# ptn_eagle7x.net
KiCad netlist of a schematic drawn in EAGLE
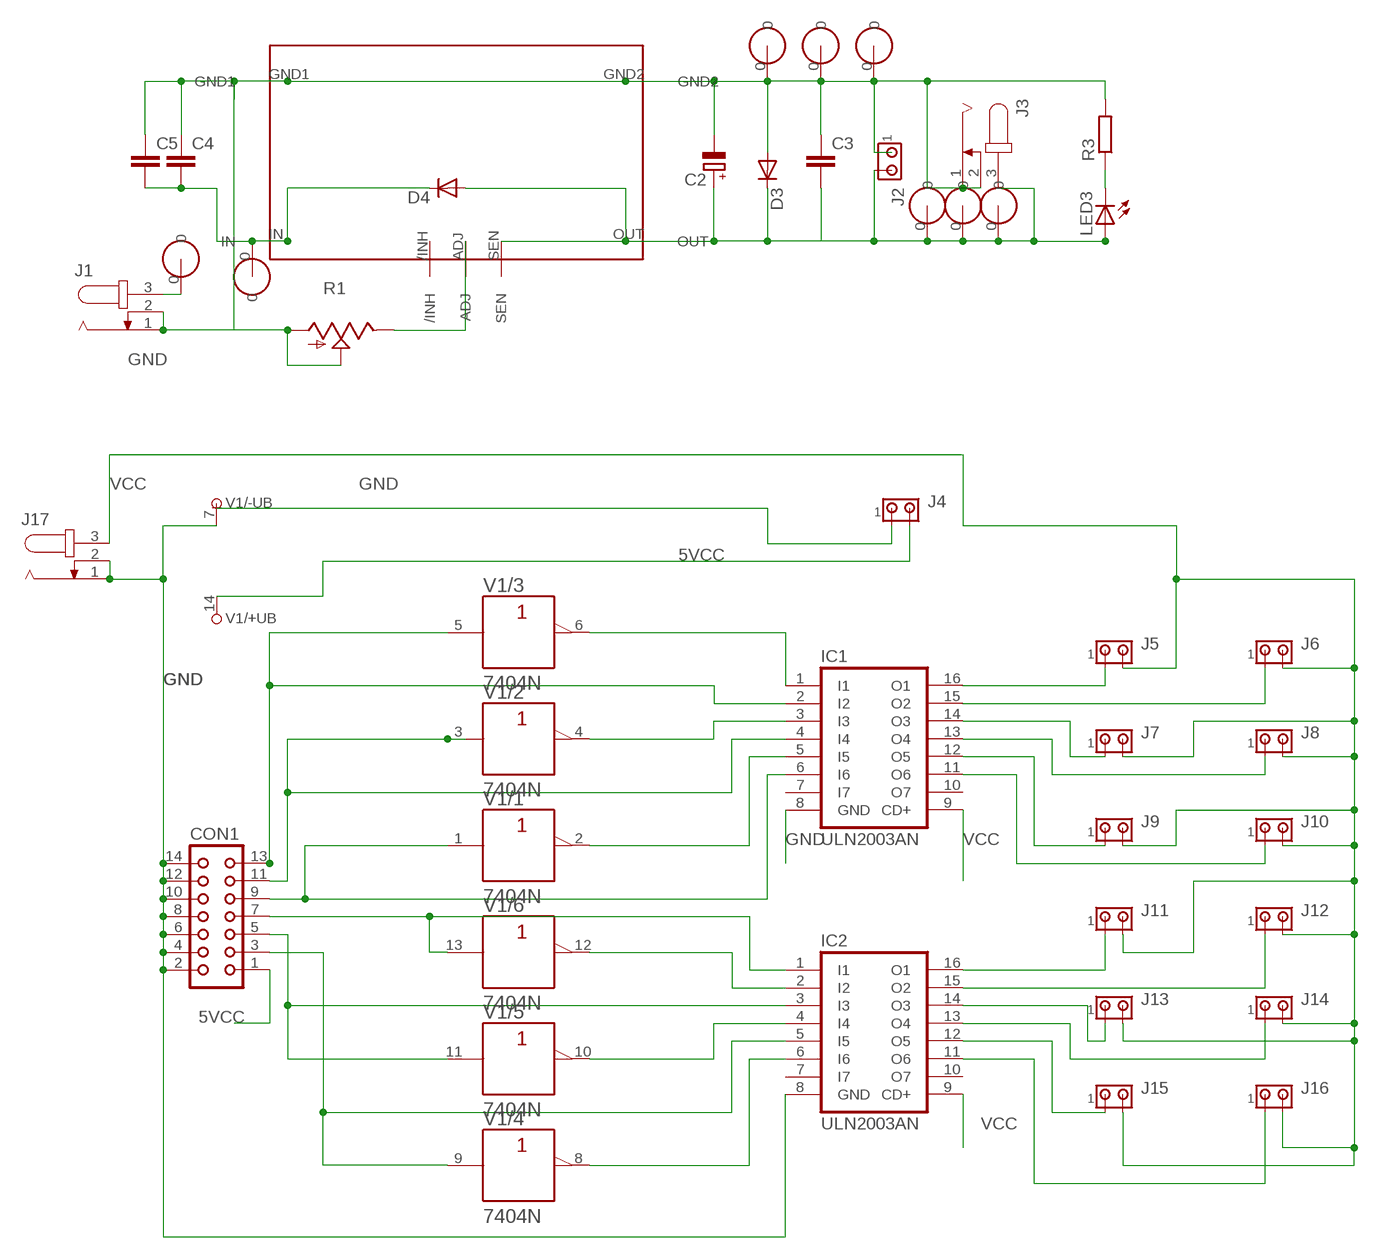
[diagram p0: schematic, sheet 1]

(export (version "E")
  (design (tool "Eeschema 10.0.6"))
  (components
    (comp (ref "C2")
      (value "CPOL-EUE3.5-8")
      (footprint "eagle-import:E3,5-8")
      (libsource (lib "eagle-import") (part "CPOL-EUE3.5-8"))
    )
    (comp (ref "C3")
      (value "C-EUC1206K")
      (footprint "eagle-import:C1206K")
      (libsource (lib "eagle-import") (part "C-EUC1206K"))
    )
    (comp (ref "C4")
      (value "C-EUC1206K")
      (footprint "eagle-import:C1206K")
      (libsource (lib "eagle-import") (part "C-EUC1206K"))
    )
    (comp (ref "C5")
      (value "C-EUC1206K")
      (footprint "eagle-import:C1206K")
      (libsource (lib "eagle-import") (part "C-EUC1206K"))
    )
    (comp (ref "CON1")
      (value "CON14")
      (footprint "eagle-import:CON14")
      (libsource (lib "eagle-import") (part "CON14"))
    )
    (comp (ref "D3")
      (value "DIODE-SMB")
      (footprint "eagle-import:SMB")
      (libsource (lib "eagle-import") (part "DIODE-SMB"))
    )
    (comp (ref "D4")
      (value "DIODE-SMB")
      (footprint "eagle-import:SMB")
      (libsource (lib "eagle-import") (part "DIODE-SMB"))
    )
    (comp (ref "IC1")
      (value "ULN2003AN")
      (footprint "eagle-import:DIL16")
      (libsource (lib "eagle-import") (part "ULN2003AN"))
    )
    (comp (ref "IC2")
      (value "ULN2003AN")
      (footprint "eagle-import:DIL16")
      (libsource (lib "eagle-import") (part "ULN2003AN"))
    )
    (comp (ref "J1")
      (value "JACK-PLUG1")
      (footprint "eagle-import:SPC4078")
      (libsource (lib "eagle-import") (part "JACK-PLUG1"))
    )
    (comp (ref "J2")
      (value "MTA02-100")
      (footprint "eagle-import:10X02MTA")
      (libsource (lib "eagle-import") (part "MTA02-100"))
    )
    (comp (ref "J3")
      (value "JACK-PLUG1")
      (footprint "eagle-import:SPC4078")
      (libsource (lib "eagle-import") (part "JACK-PLUG1"))
    )
    (comp (ref "J4")
      (value "MTA02-100")
      (footprint "eagle-import:10X02MTA")
      (libsource (lib "eagle-import") (part "MTA02-100"))
    )
    (comp (ref "J5")
      (value "MTA02-100")
      (footprint "eagle-import:10X02MTA")
      (libsource (lib "eagle-import") (part "MTA02-100"))
    )
    (comp (ref "J6")
      (value "MTA02-100")
      (footprint "eagle-import:10X02MTA")
      (libsource (lib "eagle-import") (part "MTA02-100"))
    )
    (comp (ref "J7")
      (value "MTA02-100")
      (footprint "eagle-import:10X02MTA")
      (libsource (lib "eagle-import") (part "MTA02-100"))
    )
    (comp (ref "J8")
      (value "MTA02-100")
      (footprint "eagle-import:10X02MTA")
      (libsource (lib "eagle-import") (part "MTA02-100"))
    )
    (comp (ref "J9")
      (value "MTA02-100")
      (footprint "eagle-import:10X02MTA")
      (libsource (lib "eagle-import") (part "MTA02-100"))
    )
    (comp (ref "J10")
      (value "MTA02-100")
      (footprint "eagle-import:10X02MTA")
      (libsource (lib "eagle-import") (part "MTA02-100"))
    )
    (comp (ref "J11")
      (value "MTA02-100")
      (footprint "eagle-import:10X02MTA")
      (libsource (lib "eagle-import") (part "MTA02-100"))
    )
    (comp (ref "J12")
      (value "MTA02-100")
      (footprint "eagle-import:10X02MTA")
      (libsource (lib "eagle-import") (part "MTA02-100"))
    )
    (comp (ref "J13")
      (value "MTA02-100")
      (footprint "eagle-import:10X02MTA")
      (libsource (lib "eagle-import") (part "MTA02-100"))
    )
    (comp (ref "J14")
      (value "MTA02-100")
      (footprint "eagle-import:10X02MTA")
      (libsource (lib "eagle-import") (part "MTA02-100"))
    )
    (comp (ref "J15")
      (value "MTA02-100")
      (footprint "eagle-import:10X02MTA")
      (libsource (lib "eagle-import") (part "MTA02-100"))
    )
    (comp (ref "J16")
      (value "MTA02-100")
      (footprint "eagle-import:10X02MTA")
      (libsource (lib "eagle-import") (part "MTA02-100"))
    )
    (comp (ref "J17")
      (value "JACK-PLUG1")
      (footprint "eagle-import:SPC4078")
      (libsource (lib "eagle-import") (part "JACK-PLUG1"))
    )
    (comp (ref "LED3")
      (value "LED3MM")
      (footprint "eagle-import:LED3MM")
      (libsource (lib "eagle-import") (part "LED3MM"))
    )
    (comp (ref "R1")
      (value "TRIM_US-B64Y")
      (footprint "eagle-import:B64Y")
      (libsource (lib "eagle-import") (part "TRIM_US-B64Y"))
    )
    (comp (ref "R3")
      (value "R-EU_R0603")
      (footprint "eagle-import:R0603")
      (libsource (lib "eagle-import") (part "R-EU_R0603"))
    )
    (comp (ref "U$1")
      (value "PTNPTN2")
      (footprint "eagle-import:PTN")
      (libsource (lib "eagle-import") (part "PTNPTN2"))
    )
    (comp (ref "U$2")
      (value "PAD0")
      (footprint "eagle-import:SWITCHPAD")
      (libsource (lib "eagle-import") (part "PAD0"))
    )
    (comp (ref "U$3")
      (value "PADSWITCHPAD1")
      (footprint "eagle-import:SWITCHPAD")
      (libsource (lib "eagle-import") (part "PADSWITCHPAD1"))
    )
    (comp (ref "U$4")
      (value "PADSWITCHPAD1")
      (footprint "eagle-import:SWITCHPAD")
      (libsource (lib "eagle-import") (part "PADSWITCHPAD1"))
    )
    (comp (ref "U$5")
      (value "PADSWITCHPAD1")
      (footprint "eagle-import:SWITCHPAD")
      (libsource (lib "eagle-import") (part "PADSWITCHPAD1"))
    )
    (comp (ref "U$6")
      (value "PADSWITCHPAD1")
      (footprint "eagle-import:SWITCHPAD")
      (libsource (lib "eagle-import") (part "PADSWITCHPAD1"))
    )
    (comp (ref "U$7")
      (value "PADSWITCHPAD1")
      (footprint "eagle-import:SWITCHPAD")
      (libsource (lib "eagle-import") (part "PADSWITCHPAD1"))
    )
    (comp (ref "U$8")
      (value "PADSWITCHPAD1")
      (footprint "eagle-import:SWITCHPAD")
      (libsource (lib "eagle-import") (part "PADSWITCHPAD1"))
    )
    (comp (ref "U$9")
      (value "PADSWITCHPAD1")
      (footprint "eagle-import:SWITCHPAD")
      (libsource (lib "eagle-import") (part "PADSWITCHPAD1"))
    )
    (comp (ref "V1")
      (value "7404N")
      (footprint "eagle-import:DIL14")
      (libsource (lib "eagle-import") (part "7404N"))
    )
  )
  (nets
    (net (code "1") (name "/5VCC") (class "Default")
      (node (ref "CON1") (pin "1") (pinfunction "1_1") (pintype "passive"))
      (node (ref "J4") (pin "2") (pinfunction "2_2") (pintype "passive"))
      (node (ref "V1") (pin "14") (pinfunction "+UB_14") (pintype "power_in"))
    )
    (net (code "2") (name "/GND") (class "Default")
      (node (ref "C2") (pin "-") (pinfunction "-_-") (pintype "passive"))
      (node (ref "C3") (pin "1") (pinfunction "1_1") (pintype "passive"))
      (node (ref "C4") (pin "1") (pinfunction "1_1") (pintype "passive"))
      (node (ref "C5") (pin "1") (pinfunction "1_1") (pintype "passive"))
      (node (ref "CON1") (pin "10") (pinfunction "10_10") (pintype "passive"))
      (node (ref "CON1") (pin "12") (pinfunction "12_12") (pintype "passive"))
      (node (ref "CON1") (pin "14") (pinfunction "14_14") (pintype "passive"))
      (node (ref "CON1") (pin "2") (pinfunction "2_2") (pintype "passive"))
      (node (ref "CON1") (pin "4") (pinfunction "4_4") (pintype "passive"))
      (node (ref "CON1") (pin "6") (pinfunction "6_6") (pintype "passive"))
      (node (ref "CON1") (pin "8") (pinfunction "8_8") (pintype "passive"))
      (node (ref "D3") (pin "A") (pinfunction "A_A") (pintype "passive"))
      (node (ref "IC1") (pin "8") (pinfunction "GND_8") (pintype "power_in"))
      (node (ref "IC2") (pin "8") (pinfunction "GND_8") (pintype "power_in"))
      (node (ref "J1") (pin "1") (pinfunction "1_1") (pintype "passive"))
      (node (ref "J1") (pin "2") (pinfunction "2_2") (pintype "passive"))
      (node (ref "J17") (pin "1") (pinfunction "1_1") (pintype "passive"))
      (node (ref "J17") (pin "2") (pinfunction "2_2") (pintype "passive"))
      (node (ref "J2") (pin "1") (pinfunction "1_1") (pintype "passive"))
      (node (ref "J3") (pin "1") (pinfunction "1_1") (pintype "passive"))
      (node (ref "J3") (pin "2") (pinfunction "2_2") (pintype "passive"))
      (node (ref "J4") (pin "1") (pinfunction "1_1") (pintype "passive"))
      (node (ref "R1") (pin "A") (pinfunction "A_A") (pintype "passive"))
      (node (ref "R1") (pin "S") (pinfunction "S_S") (pintype "passive"))
      (node (ref "R3") (pin "2") (pinfunction "2_2") (pintype "passive"))
      (node (ref "U$1") (pin "GND1") (pinfunction "GND1_GND1") (pintype "bidirectional"))
      (node (ref "U$1") (pin "GND2") (pinfunction "GND2_GND2") (pintype "bidirectional"))
      (node (ref "U$4") (pin "0") (pinfunction "0_0") (pintype "bidirectional"))
      (node (ref "U$6") (pin "0") (pinfunction "0_0") (pintype "bidirectional"))
      (node (ref "U$8") (pin "0") (pinfunction "0_0") (pintype "bidirectional"))
      (node (ref "V1") (pin "7") (pinfunction "-UB_7") (pintype "power_in"))
    )
    (net (code "3") (name "/VCC") (class "Default")
      (node (ref "IC1") (pin "9") (pinfunction "CD+_9") (pintype "passive"))
      (node (ref "IC2") (pin "9") (pinfunction "CD+_9") (pintype "passive"))
      (node (ref "J10") (pin "2") (pinfunction "2_2") (pintype "passive"))
      (node (ref "J11") (pin "2") (pinfunction "2_2") (pintype "passive"))
      (node (ref "J12") (pin "2") (pinfunction "2_2") (pintype "passive"))
      (node (ref "J13") (pin "2") (pinfunction "2_2") (pintype "passive"))
      (node (ref "J14") (pin "2") (pinfunction "2_2") (pintype "passive"))
      (node (ref "J15") (pin "2") (pinfunction "2_2") (pintype "passive"))
      (node (ref "J16") (pin "2") (pinfunction "2_2") (pintype "passive"))
      (node (ref "J17") (pin "3") (pinfunction "3_3") (pintype "passive"))
      (node (ref "J5") (pin "2") (pinfunction "2_2") (pintype "passive"))
      (node (ref "J6") (pin "2") (pinfunction "2_2") (pintype "passive"))
      (node (ref "J7") (pin "2") (pinfunction "2_2") (pintype "passive"))
      (node (ref "J8") (pin "2") (pinfunction "2_2") (pintype "passive"))
      (node (ref "J9") (pin "2") (pinfunction "2_2") (pintype "passive"))
    )
    (net (code "4") (name "Net-(C2-Pad+)") (class "Default")
      (node (ref "C2") (pin "+") (pinfunction "+_+") (pintype "passive"))
      (node (ref "C3") (pin "2") (pinfunction "2_2") (pintype "passive"))
      (node (ref "D3") (pin "C") (pinfunction "C_C") (pintype "passive"))
      (node (ref "D4") (pin "A") (pinfunction "A_A") (pintype "passive"))
      (node (ref "J2") (pin "2") (pinfunction "2_2") (pintype "passive"))
      (node (ref "J3") (pin "3") (pinfunction "3_3") (pintype "passive"))
      (node (ref "LED3") (pin "A") (pinfunction "A_A") (pintype "passive"))
      (node (ref "U$1") (pin "OUT") (pinfunction "OUT_OUT") (pintype "bidirectional"))
      (node (ref "U$1") (pin "SEN") (pinfunction "SEN_SEN") (pintype "bidirectional"))
      (node (ref "U$5") (pin "0") (pinfunction "0_0") (pintype "bidirectional"))
      (node (ref "U$7") (pin "0") (pinfunction "0_0") (pintype "bidirectional"))
      (node (ref "U$9") (pin "0") (pinfunction "0_0") (pintype "bidirectional"))
    )
    (net (code "5") (name "Net-(C4-Pad2)") (class "Default")
      (node (ref "C4") (pin "2") (pinfunction "2_2") (pintype "passive"))
      (node (ref "C5") (pin "2") (pinfunction "2_2") (pintype "passive"))
      (node (ref "D4") (pin "C") (pinfunction "C_C") (pintype "passive"))
      (node (ref "U$1") (pin "IN") (pinfunction "IN_IN") (pintype "bidirectional"))
      (node (ref "U$2") (pin "0") (pinfunction "0_0") (pintype "bidirectional"))
    )
    (net (code "6") (name "Net-(IC1-I1)") (class "Default")
      (node (ref "IC1") (pin "1") (pinfunction "I1_1") (pintype "input"))
      (node (ref "V1") (pin "6") (pinfunction "Y_6") (pintype "output"))
    )
    (net (code "7") (name "Net-(IC1-I2)") (class "Default")
      (node (ref "CON1") (pin "13") (pinfunction "13_13") (pintype "passive"))
      (node (ref "IC1") (pin "2") (pinfunction "I2_2") (pintype "input"))
      (node (ref "V1") (pin "5") (pinfunction "A_5") (pintype "input"))
    )
    (net (code "8") (name "Net-(IC1-I3)") (class "Default")
      (node (ref "IC1") (pin "3") (pinfunction "I3_3") (pintype "input"))
      (node (ref "V1") (pin "4") (pinfunction "Y_4") (pintype "output"))
    )
    (net (code "9") (name "Net-(IC1-I4)") (class "Default")
      (node (ref "CON1") (pin "11") (pinfunction "11_11") (pintype "passive"))
      (node (ref "IC1") (pin "4") (pinfunction "I4_4") (pintype "input"))
      (node (ref "V1") (pin "3") (pinfunction "A_3") (pintype "input"))
    )
    (net (code "10") (name "Net-(IC1-I5)") (class "Default")
      (node (ref "IC1") (pin "5") (pinfunction "I5_5") (pintype "input"))
      (node (ref "V1") (pin "2") (pinfunction "Y_2") (pintype "output"))
    )
    (net (code "11") (name "Net-(IC1-I6)") (class "Default")
      (node (ref "CON1") (pin "9") (pinfunction "9_9") (pintype "passive"))
      (node (ref "IC1") (pin "6") (pinfunction "I6_6") (pintype "input"))
      (node (ref "V1") (pin "1") (pinfunction "A_1") (pintype "input"))
    )
    (net (code "12") (name "Net-(IC1-O1)") (class "Default")
      (node (ref "IC1") (pin "16") (pinfunction "O1_16") (pintype "open_collector"))
      (node (ref "J5") (pin "1") (pinfunction "1_1") (pintype "passive"))
    )
    (net (code "13") (name "Net-(IC1-O2)") (class "Default")
      (node (ref "IC1") (pin "15") (pinfunction "O2_15") (pintype "open_collector"))
      (node (ref "J6") (pin "1") (pinfunction "1_1") (pintype "passive"))
    )
    (net (code "14") (name "Net-(IC1-O3)") (class "Default")
      (node (ref "IC1") (pin "14") (pinfunction "O3_14") (pintype "open_collector"))
      (node (ref "J7") (pin "1") (pinfunction "1_1") (pintype "passive"))
    )
    (net (code "15") (name "Net-(IC1-O4)") (class "Default")
      (node (ref "IC1") (pin "13") (pinfunction "O4_13") (pintype "open_collector"))
      (node (ref "J8") (pin "1") (pinfunction "1_1") (pintype "passive"))
    )
    (net (code "16") (name "Net-(IC1-O5)") (class "Default")
      (node (ref "IC1") (pin "12") (pinfunction "O5_12") (pintype "open_collector"))
      (node (ref "J9") (pin "1") (pinfunction "1_1") (pintype "passive"))
    )
    (net (code "17") (name "Net-(IC1-O6)") (class "Default")
      (node (ref "IC1") (pin "11") (pinfunction "O6_11") (pintype "open_collector"))
      (node (ref "J10") (pin "1") (pinfunction "1_1") (pintype "passive"))
    )
    (net (code "18") (name "Net-(IC2-I1)") (class "Default")
      (node (ref "CON1") (pin "7") (pinfunction "7_7") (pintype "passive"))
      (node (ref "IC2") (pin "1") (pinfunction "I1_1") (pintype "input"))
      (node (ref "V1") (pin "13") (pinfunction "A_13") (pintype "input"))
    )
    (net (code "19") (name "Net-(IC2-I2)") (class "Default")
      (node (ref "IC2") (pin "2") (pinfunction "I2_2") (pintype "input"))
      (node (ref "V1") (pin "12") (pinfunction "Y_12") (pintype "output"))
    )
    (net (code "20") (name "Net-(IC2-I3)") (class "Default")
      (node (ref "CON1") (pin "5") (pinfunction "5_5") (pintype "passive"))
      (node (ref "IC2") (pin "3") (pinfunction "I3_3") (pintype "input"))
      (node (ref "V1") (pin "11") (pinfunction "A_11") (pintype "input"))
    )
    (net (code "21") (name "Net-(IC2-I4)") (class "Default")
      (node (ref "IC2") (pin "4") (pinfunction "I4_4") (pintype "input"))
      (node (ref "V1") (pin "10") (pinfunction "Y_10") (pintype "output"))
    )
    (net (code "22") (name "Net-(IC2-I5)") (class "Default")
      (node (ref "CON1") (pin "3") (pinfunction "3_3") (pintype "passive"))
      (node (ref "IC2") (pin "5") (pinfunction "I5_5") (pintype "input"))
      (node (ref "V1") (pin "9") (pinfunction "A_9") (pintype "input"))
    )
    (net (code "23") (name "Net-(IC2-I6)") (class "Default")
      (node (ref "IC2") (pin "6") (pinfunction "I6_6") (pintype "input"))
      (node (ref "V1") (pin "8") (pinfunction "Y_8") (pintype "output"))
    )
    (net (code "24") (name "Net-(IC2-O1)") (class "Default")
      (node (ref "IC2") (pin "16") (pinfunction "O1_16") (pintype "open_collector"))
      (node (ref "J11") (pin "1") (pinfunction "1_1") (pintype "passive"))
    )
    (net (code "25") (name "Net-(IC2-O2)") (class "Default")
      (node (ref "IC2") (pin "15") (pinfunction "O2_15") (pintype "open_collector"))
      (node (ref "J12") (pin "1") (pinfunction "1_1") (pintype "passive"))
    )
    (net (code "26") (name "Net-(IC2-O3)") (class "Default")
      (node (ref "IC2") (pin "14") (pinfunction "O3_14") (pintype "open_collector"))
      (node (ref "J13") (pin "1") (pinfunction "1_1") (pintype "passive"))
    )
    (net (code "27") (name "Net-(IC2-O4)") (class "Default")
      (node (ref "IC2") (pin "13") (pinfunction "O4_13") (pintype "open_collector"))
      (node (ref "J14") (pin "1") (pinfunction "1_1") (pintype "passive"))
    )
    (net (code "28") (name "Net-(IC2-O5)") (class "Default")
      (node (ref "IC2") (pin "12") (pinfunction "O5_12") (pintype "open_collector"))
      (node (ref "J15") (pin "1") (pinfunction "1_1") (pintype "passive"))
    )
    (net (code "29") (name "Net-(IC2-O6)") (class "Default")
      (node (ref "IC2") (pin "11") (pinfunction "O6_11") (pintype "open_collector"))
      (node (ref "J16") (pin "1") (pinfunction "1_1") (pintype "passive"))
    )
    (net (code "30") (name "Net-(J1-Pad3)") (class "Default")
      (node (ref "J1") (pin "3") (pinfunction "3_3") (pintype "passive"))
      (node (ref "U$3") (pin "0") (pinfunction "0_0") (pintype "bidirectional"))
    )
    (net (code "31") (name "Net-(LED3-C)") (class "Default")
      (node (ref "LED3") (pin "K") (pinfunction "C_K") (pintype "passive"))
      (node (ref "R3") (pin "1") (pinfunction "1_1") (pintype "passive"))
    )
    (net (code "32") (name "Net-(R1-PadE)") (class "Default")
      (node (ref "R1") (pin "E") (pinfunction "E_E") (pintype "passive"))
      (node (ref "U$1") (pin "ADJ") (pinfunction "ADJ_ADJ") (pintype "bidirectional"))
    )
    (net (code "33") (name "unconnected-(IC1-I7-Pad7)") (class "Default")
      (node (ref "IC1") (pin "7") (pinfunction "I7_7") (pintype "input"))
    )
    (net (code "34") (name "unconnected-(IC1-O7-Pad10)") (class "Default")
      (node (ref "IC1") (pin "10") (pinfunction "O7_10") (pintype "open_collector"))
    )
    (net (code "35") (name "unconnected-(IC2-I7-Pad7)") (class "Default")
      (node (ref "IC2") (pin "7") (pinfunction "I7_7") (pintype "input"))
    )
    (net (code "36") (name "unconnected-(IC2-O7-Pad10)") (class "Default")
      (node (ref "IC2") (pin "10") (pinfunction "O7_10") (pintype "open_collector"))
    )
    (net (code "37") (name "unconnected-(U$1-Pad{slash}INH)") (class "Default")
      (node (ref "U$1") (pin "/INH") (pinfunction "/INH_/INH") (pintype "bidirectional"))
    )
  )
)
